# Teensy32.net
KiCad netlist of a schematic drawn in Altium Designer
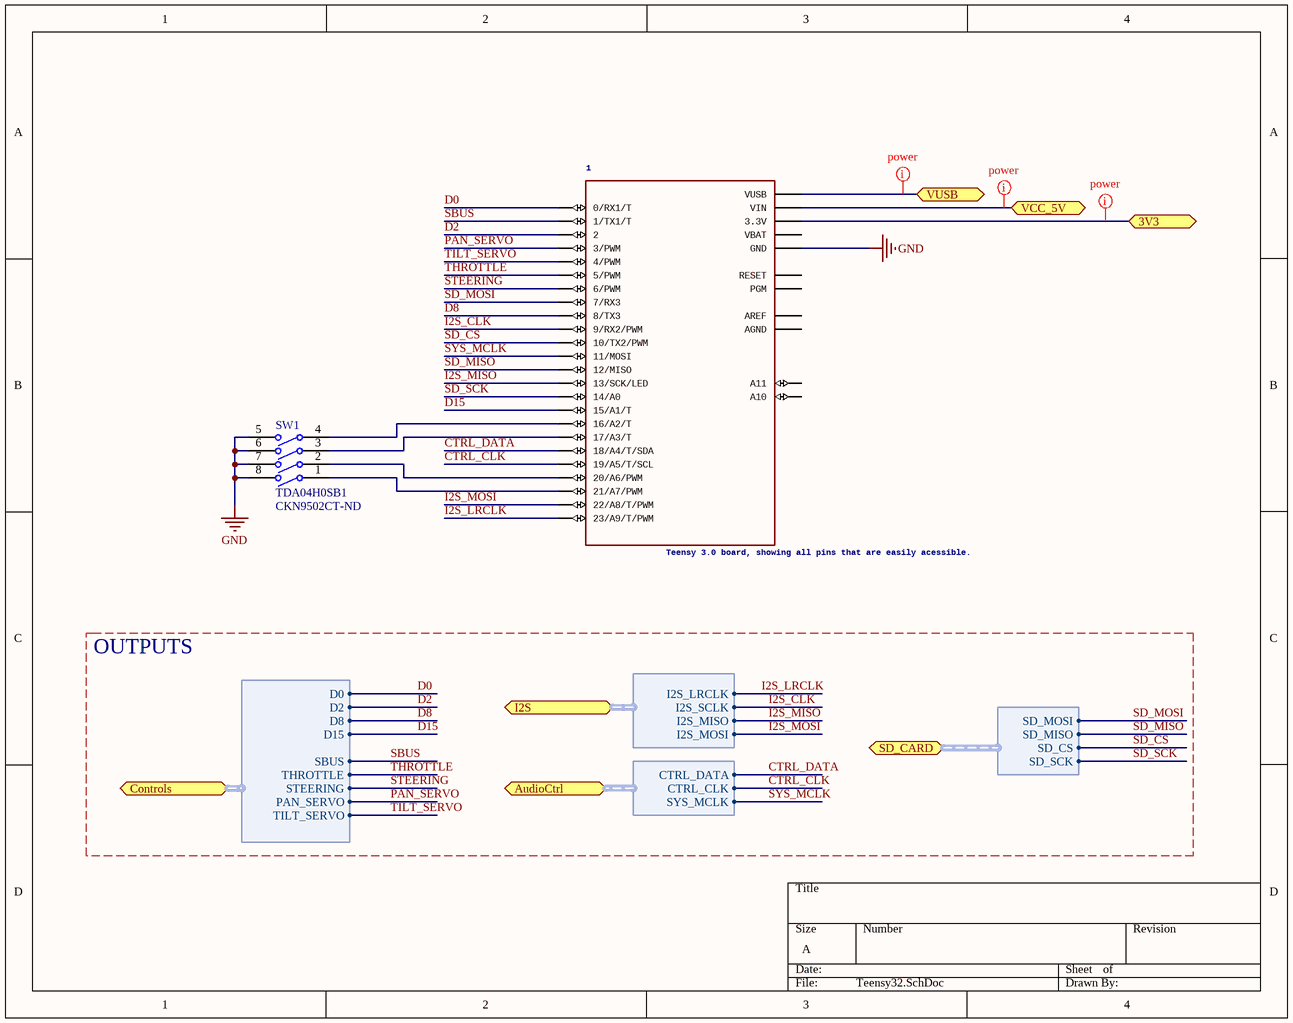
[diagram p0: Teensy32.SchDoc]

(export (version "E")
  (design (tool "Eeschema 10.0.6"))
  (components
    (comp (ref "1")
      (value "Teensy 3.0 board, showing all pins that are easily acessible.")
      (footprint "TEENSY_3.0-3.2&LC_ALL_PINS")
      (libsource (lib "Teensy_3_and_LC_Series_Boards_v1") (part "TEENSY_3.0_ALL_PINS"))
    )
    (comp (ref "SW1")
      (value "TDA04H0SB1")
      (footprint "CKCP-TDA04H0SB1R_V")
      (fields (field (name "SUPPLIER PART NUMBER 1") "CKN9502CT-ND"))
      (libsource (lib "Altium Content Vault") (part "SW-SPST-8"))
    )
  )
  (nets
    (net (code "5") (name "/3V3") (class "Default")
      (node (ref "1") (pin "3.3V_3.3V1") (pinfunction "3.3V_3.3V_3.3V1") (pintype "power_in"))
    )
    (net (code "6") (name "/CTRL_CLK") (class "Default")
      (node (ref "1") (pin "19/A5") (pinfunction "19/A5/T/SCL_19/A5") (pintype "bidirectional"))
    )
    (net (code "7") (name "/CTRL_DATA") (class "Default")
      (node (ref "1") (pin "18/A4") (pinfunction "18/A4/T/SDA_18/A4") (pintype "bidirectional"))
    )
    (net (code "8") (name "/D0") (class "Default")
      (node (ref "1") (pin "0") (pinfunction "0/RX1/T_0") (pintype "bidirectional"))
    )
    (net (code "9") (name "/D2") (class "Default")
      (node (ref "1") (pin "2") (pinfunction "2_2") (pintype "bidirectional"))
    )
    (net (code "10") (name "/D8") (class "Default")
      (node (ref "1") (pin "8") (pinfunction "8/TX3_8") (pintype "bidirectional"))
    )
    (net (code "11") (name "/D15") (class "Default")
      (node (ref "1") (pin "15/A1") (pinfunction "15/A1/T_15/A1") (pintype "bidirectional"))
    )
    (net (code "12") (name "/I2S_CLK") (class "Default")
      (node (ref "1") (pin "9") (pinfunction "9/RX2/PWM_9") (pintype "bidirectional"))
    )
    (net (code "13") (name "/I2S_LRCLK") (class "Default")
      (node (ref "1") (pin "23/A9") (pinfunction "23/A9/T/PWM_23/A9") (pintype "bidirectional"))
    )
    (net (code "14") (name "/I2S_MISO") (class "Default")
      (node (ref "1") (pin "13") (pinfunction "13/SCK/LED_13") (pintype "bidirectional"))
    )
    (net (code "15") (name "/I2S_MOSI") (class "Default")
      (node (ref "1") (pin "22/A8") (pinfunction "22/A8/T/PWM_22/A8") (pintype "bidirectional"))
    )
    (net (code "16") (name "/PAN_SERVO") (class "Default")
      (node (ref "1") (pin "3") (pinfunction "3/PWM_3") (pintype "bidirectional"))
    )
    (net (code "17") (name "/SBUS") (class "Default")
      (node (ref "1") (pin "1") (pinfunction "1/TX1/T_1") (pintype "bidirectional"))
    )
    (net (code "18") (name "/SD_CS") (class "Default")
      (node (ref "1") (pin "10") (pinfunction "10/TX2/PWM_10") (pintype "bidirectional"))
    )
    (net (code "19") (name "/SD_MISO") (class "Default")
      (node (ref "1") (pin "12") (pinfunction "12/MISO_12") (pintype "bidirectional"))
    )
    (net (code "20") (name "/SD_MOSI") (class "Default")
      (node (ref "1") (pin "7") (pinfunction "7/RX3_7") (pintype "bidirectional"))
    )
    (net (code "21") (name "/SD_SCK") (class "Default")
      (node (ref "1") (pin "14/A0") (pinfunction "14/A0_14/A0") (pintype "bidirectional"))
    )
    (net (code "22") (name "/STEERING") (class "Default")
      (node (ref "1") (pin "6") (pinfunction "6/PWM_6") (pintype "bidirectional"))
    )
    (net (code "23") (name "/SYS_MCLK") (class "Default")
      (node (ref "1") (pin "11") (pinfunction "11/MOSI_11") (pintype "bidirectional"))
    )
    (net (code "24") (name "/THROTTLE") (class "Default")
      (node (ref "1") (pin "5") (pinfunction "5/PWM_5") (pintype "bidirectional"))
    )
    (net (code "25") (name "/TILT_SERVO") (class "Default")
      (node (ref "1") (pin "4") (pinfunction "4/PWM_4") (pintype "bidirectional"))
    )
    (net (code "26") (name "/VCC_5V") (class "Default")
      (node (ref "1") (pin "VIN") (pinfunction "VIN_VIN") (pintype "power_in"))
    )
    (net (code "27") (name "/VUSB") (class "Default")
      (node (ref "1") (pin "VUSB") (pinfunction "VUSB_VUSB") (pintype "power_in"))
    )
    (net (code "32") (name "GND") (class "Default")
      (node (ref "1") (pin "GND_GND1") (pinfunction "GND_GND_GND1") (pintype "power_in"))
      (node (ref "SW1") (pin "5") (pinfunction "5_5") (pintype "passive"))
      (node (ref "SW1") (pin "6") (pinfunction "6_6") (pintype "passive"))
      (node (ref "SW1") (pin "7") (pinfunction "7_7") (pintype "passive"))
      (node (ref "SW1") (pin "8") (pinfunction "8_8") (pintype "passive"))
    )
    (net (code "33") (name "Net-(1-16{slash}A2{slash}T)") (class "Default")
      (node (ref "1") (pin "16/A2") (pinfunction "16/A2/T_16/A2") (pintype "bidirectional"))
      (node (ref "SW1") (pin "4") (pinfunction "4_4") (pintype "passive"))
    )
    (net (code "34") (name "Net-(1-17{slash}A3{slash}T)") (class "Default")
      (node (ref "1") (pin "17/A3") (pinfunction "17/A3/T_17/A3") (pintype "bidirectional"))
      (node (ref "SW1") (pin "3") (pinfunction "3_3") (pintype "passive"))
    )
    (net (code "35") (name "Net-(1-20{slash}A6{slash}PWM)") (class "Default")
      (node (ref "1") (pin "20/A6") (pinfunction "20/A6/PWM_20/A6") (pintype "bidirectional"))
      (node (ref "SW1") (pin "2") (pinfunction "2_2") (pintype "passive"))
    )
    (net (code "36") (name "Net-(1-21{slash}A7{slash}PWM)") (class "Default")
      (node (ref "1") (pin "21/A7") (pinfunction "21/A7/PWM_21/A7") (pintype "bidirectional"))
      (node (ref "SW1") (pin "1") (pinfunction "1_1") (pintype "passive"))
    )
    (net (code "37") (name "unconnected-(1-PadA10)") (class "Default")
      (node (ref "1") (pin "A10") (pinfunction "A10_A10") (pintype "bidirectional"))
    )
    (net (code "38") (name "unconnected-(1-PadA11)") (class "Default")
      (node (ref "1") (pin "A11") (pinfunction "A11_A11") (pintype "bidirectional"))
    )
    (net (code "39") (name "unconnected-(1-PadAGND)") (class "Default")
      (node (ref "1") (pin "AGND") (pinfunction "AGND_AGND") (pintype "power_in"))
    )
    (net (code "40") (name "unconnected-(1-PadAREF)") (class "Default")
      (node (ref "1") (pin "AREF") (pinfunction "AREF_AREF") (pintype "passive"))
    )
    (net (code "41") (name "unconnected-(1-PadPGM)") (class "Default")
      (node (ref "1") (pin "PGM") (pinfunction "PGM_PGM") (pintype "passive"))
    )
    (net (code "42") (name "unconnected-(1-PadVBAT)") (class "Default")
      (node (ref "1") (pin "VBAT") (pinfunction "VBAT_VBAT") (pintype "power_in"))
    )
    (net (code "43") (name "unconnected-(1-RESET-PadRESET{slash}DAC)") (class "Default")
      (node (ref "1") (pin "RESET/DAC") (pinfunction "RESET_RESET/DAC") (pintype "passive"))
    )
  )
)
